# H_Bridge.net
KiCad netlist of a schematic drawn in Altium Designer
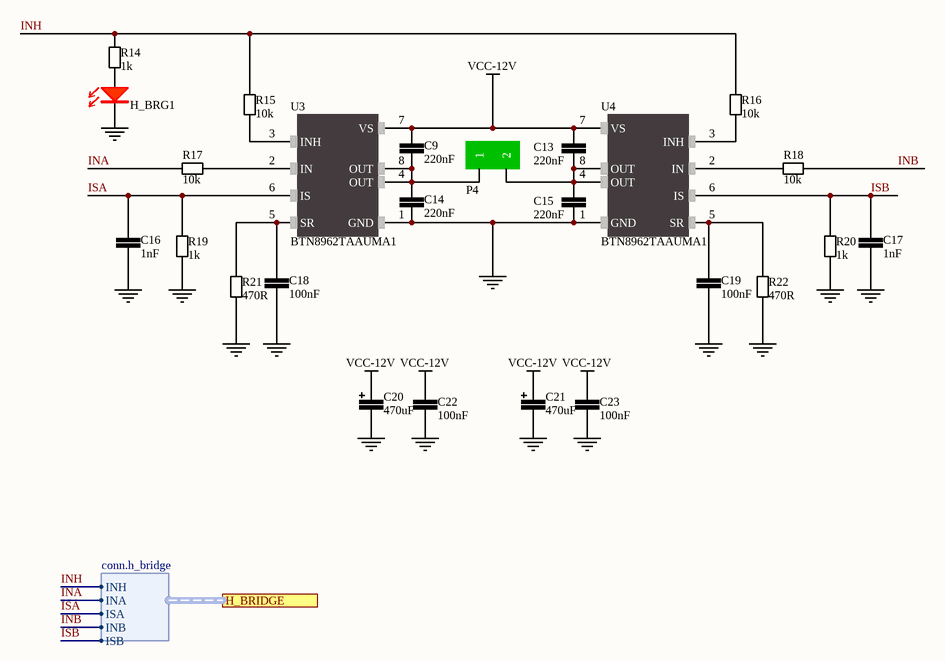
[diagram p0: H_Bridge.SchDoc]

(export (version "E")
  (design (tool "Eeschema 10.0.6"))
  (components
    (comp (ref "C9")
      (value "220nF")
      (footprint "CER_0805")
      (description "CAP CER 220n 10V X5R 10% 0805")
      (libsource (lib "Capacitors") (part "00002205"))
    )
    (comp (ref "C13")
      (value "220nF")
      (footprint "CER_0805")
      (description "CAP CER 220n 10V X5R 10% 0805")
      (libsource (lib "Capacitors") (part "00002205"))
    )
    (comp (ref "C14")
      (value "220nF")
      (footprint "CER_0805")
      (description "CAP CER 220n 10V X5R 10% 0805")
      (libsource (lib "Capacitors") (part "00002205"))
    )
    (comp (ref "C15")
      (value "220nF")
      (footprint "CER_0805")
      (description "CAP CER 220n 10V X5R 10% 0805")
      (libsource (lib "Capacitors") (part "00002205"))
    )
    (comp (ref "C16")
      (value "1nF")
      (footprint "CER_0805")
      (description "CAP CER 1n 50V X7R 10% 0805")
      (libsource (lib "Capacitors") (part "00002105_1"))
    )
    (comp (ref "C17")
      (value "1nF")
      (footprint "CER_0805")
      (description "CAP CER 1n 50V X7R 10% 0805")
      (libsource (lib "Capacitors") (part "00002105_1"))
    )
    (comp (ref "C18")
      (value "100nF")
      (footprint "CER_0805")
      (description "CAP CER 100n 50V X7R 10% 0805")
      (libsource (lib "Capacitors") (part "00002105"))
    )
    (comp (ref "C19")
      (value "100nF")
      (footprint "CER_0805")
      (description "CAP CER 100n 50V X7R 10% 0805")
      (libsource (lib "Capacitors") (part "00002105"))
    )
    (comp (ref "C20")
      (value "470uF")
      (footprint "CAP10X20_RADIAL")
      (description "CAP ALU 470u 25V 20%")
      (libsource (lib "Capacitors") (part "00004707"))
    )
    (comp (ref "C21")
      (value "470uF")
      (footprint "CAP10X20_RADIAL")
      (description "CAP ALU 470u 25V 20%")
      (libsource (lib "Capacitors") (part "00004707"))
    )
    (comp (ref "C22")
      (value "100nF")
      (footprint "CER_0805")
      (description "CAP CER 100n 50V X7R 10% 0805")
      (libsource (lib "Capacitors") (part "00002105"))
    )
    (comp (ref "C23")
      (value "100nF")
      (footprint "CER_0805")
      (description "CAP CER 100n 50V X7R 10% 0805")
      (libsource (lib "Capacitors") (part "00002105"))
    )
    (comp (ref "H_BRG1")
      (value "LED RED")
      (footprint "LED_RED_0805")
      (description "LED RED 0805")
      (fields
        (field (name "MANUFACTURER") "BRIGHT LED ELECTRONICS")
        (field (name "MANUFACTURER PART NUMBER") "BL-HUB35A-AV-TRB")
      )
      (libsource (lib "Discrete_Semiconductor") (part "LED_RED_0805"))
    )
    (comp (ref "P4")
      (value "*")
      (footprint "Electro_Mechanical:MOTOR_CON")
      (description "CONNECTOR FOR MOTOR OUTPUT")
      (libsource (lib "Electro_Mechanical") (part "MOT_CONN"))
    )
    (comp (ref "R14")
      (value "1k")
      (footprint "RESC2013X38N-0805-NOOVERLAY")
      (description "RES SMD 1 kOhm 1/8W 0805")
      (fields (field (name "POWER") "0.125W, 1/8W"))
      (libsource (lib "Resistors") (part "00001001"))
    )
    (comp (ref "R15")
      (value "10k")
      (footprint "RESC2013X38N-0805-NOOVERLAY")
      (description "RES SMD 10 kOhm 1/8W 0805")
      (libsource (lib "") (part "000001002_1"))
    )
    (comp (ref "R16")
      (value "10k")
      (footprint "RESC2013X38N-0805-NOOVERLAY")
      (description "RES SMD 10 kOhm 1/8W 0805")
      (libsource (lib "") (part "000001002_1"))
    )
    (comp (ref "R17")
      (value "10k")
      (footprint "RESC2013X38N-0805-NOOVERLAY")
      (description "RES SMD 10 kOhm 1/8W 0805")
      (libsource (lib "Resistors") (part "000001002"))
    )
    (comp (ref "R18")
      (value "10k")
      (footprint "RESC2013X38N-0805-NOOVERLAY")
      (description "RES SMD 10 kOhm 1/8W 0805")
      (libsource (lib "") (part "000001002_2"))
    )
    (comp (ref "R19")
      (value "1k")
      (footprint "RESC2013X38N-0805-NOOVERLAY")
      (description "RES SMD 1 kOhm 1/8W 0805")
      (fields (field (name "POWER") "0.125W, 1/8W"))
      (libsource (lib "Resistors") (part "00001001"))
    )
    (comp (ref "R20")
      (value "1k")
      (footprint "RESC2013X38N-0805-NOOVERLAY")
      (description "RES SMD 1 kOhm 1/8W 0805")
      (fields (field (name "POWER") "0.125W, 1/8W"))
      (libsource (lib "Resistors") (part "00001001"))
    )
    (comp (ref "R21")
      (value "470R")
      (footprint "RESC2013X38N-0805-NOOVERLAY")
      (description "RES SMD 470 Ohm 1/8W 0805")
      (fields (field (name "POWER") "0.125W, 1/8W"))
      (libsource (lib "Resistors") (part "00004700"))
    )
    (comp (ref "R22")
      (value "470R")
      (footprint "RESC2013X38N-0805-NOOVERLAY")
      (description "RES SMD 470 Ohm 1/8W 0805")
      (fields (field (name "POWER") "0.125W, 1/8W"))
      (libsource (lib "Resistors") (part "00004700"))
    )
    (comp (ref "U3")
      (value "BTN8962TAAUMA1")
      (footprint "TO263-7")
      (description "IC MOTOR DRIVER PAR TO263-7")
      (libsource (lib "") (part "00000010_1"))
    )
    (comp (ref "U4")
      (value "BTN8962TAAUMA1")
      (footprint "TO263-7")
      (description "IC MOTOR DRIVER PAR TO263-7")
      (libsource (lib "Integrated_circuits") (part "00000010"))
    )
  )
  (nets
    (net (code "2") (name "/INA") (class "Default")
      (node (ref "R17") (pin "2") (pinfunction "2_2") (pintype "passive"))
    )
    (net (code "3") (name "/INB") (class "Default")
      (node (ref "R18") (pin "2") (pinfunction "2_2") (pintype "passive"))
    )
    (net (code "4") (name "/INH") (class "Default")
      (node (ref "R14") (pin "2") (pinfunction "2_2") (pintype "passive"))
      (node (ref "R15") (pin "2") (pinfunction "2_2") (pintype "passive"))
      (node (ref "R16") (pin "2") (pinfunction "2_2") (pintype "passive"))
    )
    (net (code "5") (name "/ISA") (class "Default")
      (node (ref "C16") (pin "2") (pinfunction "2_2") (pintype "passive"))
      (node (ref "R19") (pin "2") (pinfunction "2_2") (pintype "passive"))
      (node (ref "U3") (pin "6") (pinfunction "IS_6") (pintype "passive"))
    )
    (net (code "6") (name "/ISB") (class "Default")
      (node (ref "C17") (pin "2") (pinfunction "2_2") (pintype "passive"))
      (node (ref "R20") (pin "2") (pinfunction "2_2") (pintype "passive"))
      (node (ref "U4") (pin "6") (pinfunction "IS_6") (pintype "passive"))
    )
    (net (code "8") (name "GND") (class "Default")
      (node (ref "C14") (pin "1") (pinfunction "1_1") (pintype "passive"))
      (node (ref "C15") (pin "1") (pinfunction "1_1") (pintype "passive"))
      (node (ref "C16") (pin "1") (pinfunction "1_1") (pintype "passive"))
      (node (ref "C17") (pin "1") (pinfunction "1_1") (pintype "passive"))
      (node (ref "C18") (pin "1") (pinfunction "1_1") (pintype "passive"))
      (node (ref "C19") (pin "1") (pinfunction "1_1") (pintype "passive"))
      (node (ref "C20") (pin "2") (pinfunction "2_2") (pintype "passive"))
      (node (ref "C21") (pin "2") (pinfunction "2_2") (pintype "passive"))
      (node (ref "C22") (pin "1") (pinfunction "1_1") (pintype "passive"))
      (node (ref "C23") (pin "1") (pinfunction "1_1") (pintype "passive"))
      (node (ref "H_BRG1") (pin "1") (pinfunction "C_1") (pintype "passive"))
      (node (ref "R19") (pin "1") (pinfunction "1_1") (pintype "passive"))
      (node (ref "R20") (pin "1") (pinfunction "1_1") (pintype "passive"))
      (node (ref "R21") (pin "1") (pinfunction "1_1") (pintype "passive"))
      (node (ref "R22") (pin "1") (pinfunction "1_1") (pintype "passive"))
      (node (ref "U3") (pin "1") (pinfunction "GND_1") (pintype "passive"))
      (node (ref "U4") (pin "1") (pinfunction "GND_1") (pintype "passive"))
    )
    (net (code "9") (name "Net-(C13-Pad2)") (class "Default")
      (node (ref "C13") (pin "2") (pinfunction "2_2") (pintype "passive"))
      (node (ref "C15") (pin "2") (pinfunction "2_2") (pintype "passive"))
      (node (ref "P4") (pin "2") (pinfunction "2_2") (pintype "passive"))
      (node (ref "U4") (pin "4") (pinfunction "OUT_4") (pintype "passive"))
      (node (ref "U4") (pin "8") (pinfunction "OUT_8") (pintype "passive"))
    )
    (net (code "10") (name "Net-(C14-Pad2)") (class "Default")
      (node (ref "C14") (pin "2") (pinfunction "2_2") (pintype "passive"))
      (node (ref "C9") (pin "1") (pinfunction "1_1") (pintype "passive"))
      (node (ref "P4") (pin "1") (pinfunction "1_1") (pintype "passive"))
      (node (ref "U3") (pin "4") (pinfunction "OUT_4") (pintype "passive"))
      (node (ref "U3") (pin "8") (pinfunction "OUT_8") (pintype "passive"))
    )
    (net (code "11") (name "Net-(H_BRG1-A)") (class "Default")
      (node (ref "H_BRG1") (pin "2") (pinfunction "A_2") (pintype "passive"))
      (node (ref "R14") (pin "1") (pinfunction "1_1") (pintype "passive"))
    )
    (net (code "12") (name "Net-(U3-IN)") (class "Default")
      (node (ref "R17") (pin "1") (pinfunction "1_1") (pintype "passive"))
      (node (ref "U3") (pin "2") (pinfunction "IN_2") (pintype "passive"))
    )
    (net (code "13") (name "Net-(U3-INH)") (class "Default")
      (node (ref "R15") (pin "1") (pinfunction "1_1") (pintype "passive"))
      (node (ref "U3") (pin "3") (pinfunction "INH_3") (pintype "passive"))
    )
    (net (code "14") (name "Net-(U3-SR)") (class "Default")
      (node (ref "C18") (pin "2") (pinfunction "2_2") (pintype "passive"))
      (node (ref "R21") (pin "2") (pinfunction "2_2") (pintype "passive"))
      (node (ref "U3") (pin "5") (pinfunction "SR_5") (pintype "passive"))
    )
    (net (code "15") (name "Net-(U4-IN)") (class "Default")
      (node (ref "R18") (pin "1") (pinfunction "1_1") (pintype "passive"))
      (node (ref "U4") (pin "2") (pinfunction "IN_2") (pintype "passive"))
    )
    (net (code "16") (name "Net-(U4-INH)") (class "Default")
      (node (ref "R16") (pin "1") (pinfunction "1_1") (pintype "passive"))
      (node (ref "U4") (pin "3") (pinfunction "INH_3") (pintype "passive"))
    )
    (net (code "17") (name "Net-(U4-SR)") (class "Default")
      (node (ref "C19") (pin "2") (pinfunction "2_2") (pintype "passive"))
      (node (ref "R22") (pin "2") (pinfunction "2_2") (pintype "passive"))
      (node (ref "U4") (pin "5") (pinfunction "SR_5") (pintype "passive"))
    )
    (net (code "18") (name "VCC-12V") (class "Default")
      (node (ref "C13") (pin "1") (pinfunction "1_1") (pintype "passive"))
      (node (ref "C20") (pin "1") (pinfunction "1_1") (pintype "passive"))
      (node (ref "C21") (pin "1") (pinfunction "1_1") (pintype "passive"))
      (node (ref "C22") (pin "2") (pinfunction "2_2") (pintype "passive"))
      (node (ref "C23") (pin "2") (pinfunction "2_2") (pintype "passive"))
      (node (ref "C9") (pin "2") (pinfunction "2_2") (pintype "passive"))
      (node (ref "U3") (pin "7") (pinfunction "VS_7") (pintype "passive"))
      (node (ref "U4") (pin "7") (pinfunction "VS_7") (pintype "passive"))
    )
  )
)
